# Dual_Power_Suppl_Center_T.net
KiCad netlist of a schematic drawn in EAGLE
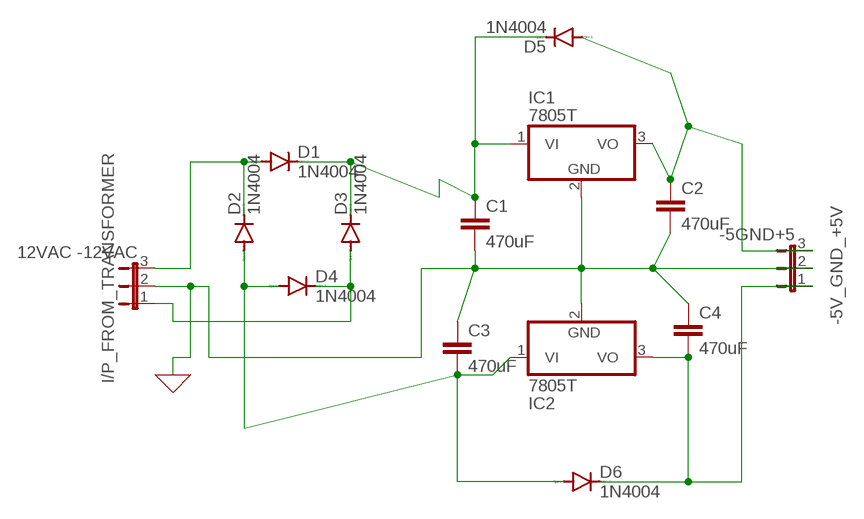
[diagram p0: schematic, sheet 1]

(export (version "E")
  (design (tool "Eeschema 10.0.6"))
  (components
    (comp (ref "-5V_GND_+5V")
      (value "-5GND+5")
      (footprint "eagle-import:JP2")
      (libsource (lib "eagle-import") (part "JP2E"))
    )
    (comp (ref "C1")
      (value "470uF")
      (footprint "eagle-import:C2.5-3")
      (libsource (lib "eagle-import") (part "C2,5-3"))
    )
    (comp (ref "C2")
      (value "470uF")
      (footprint "eagle-import:C2.5-3")
      (libsource (lib "eagle-import") (part "C2,5-3"))
    )
    (comp (ref "C3")
      (value "470uF")
      (footprint "eagle-import:C2.5-3")
      (libsource (lib "eagle-import") (part "C2,5-3"))
    )
    (comp (ref "C4")
      (value "470uF")
      (footprint "eagle-import:C2.5-3")
      (libsource (lib "eagle-import") (part "C2,5-3"))
    )
    (comp (ref "D1")
      (value "1N4004")
      (footprint "eagle-import:DO41-10")
      (libsource (lib "eagle-import") (part "1N4004"))
    )
    (comp (ref "D2")
      (value "1N4004")
      (footprint "eagle-import:DO41-10")
      (libsource (lib "eagle-import") (part "1N4004"))
    )
    (comp (ref "D3")
      (value "1N4004")
      (footprint "eagle-import:DO41-10")
      (libsource (lib "eagle-import") (part "1N4004"))
    )
    (comp (ref "D4")
      (value "1N4004")
      (footprint "eagle-import:DO41-10")
      (libsource (lib "eagle-import") (part "1N4004"))
    )
    (comp (ref "D5")
      (value "1N4004")
      (footprint "eagle-import:DO41-10")
      (libsource (lib "eagle-import") (part "1N4004"))
    )
    (comp (ref "D6")
      (value "1N4004")
      (footprint "eagle-import:DO41-10")
      (libsource (lib "eagle-import") (part "1N4004"))
    )
    (comp (ref "I/P_FROM_TRANSFORMER")
      (value "12VAC -12VAC")
      (footprint "eagle-import:JP2")
      (libsource (lib "eagle-import") (part "JP2E"))
    )
    (comp (ref "IC1")
      (value "7805T")
      (footprint "eagle-import:TO220H")
      (libsource (lib "eagle-import") (part "78T05"))
    )
    (comp (ref "IC2")
      (value "7805T")
      (footprint "eagle-import:TO220H")
      (libsource (lib "eagle-import") (part "78T05"))
    )
  )
  (nets
    (net (code "1") (name "GND") (class "Default")
      (node (ref "-5V_GND_+5V") (pin "2") (pinfunction "2_2") (pintype "passive"))
      (node (ref "C1") (pin "2") (pinfunction "2_2") (pintype "passive"))
      (node (ref "C2") (pin "2") (pinfunction "2_2") (pintype "passive"))
      (node (ref "C3") (pin "1") (pinfunction "1_1") (pintype "passive"))
      (node (ref "C4") (pin "1") (pinfunction "1_1") (pintype "passive"))
      (node (ref "I/P_FROM_TRANSFORMER") (pin "2") (pinfunction "2_2") (pintype "passive"))
      (node (ref "IC1") (pin "2") (pinfunction "GND_2") (pintype "passive"))
      (node (ref "IC2") (pin "2") (pinfunction "GND_2") (pintype "passive"))
    )
    (net (code "2") (name "Net-(D1-PadA)") (class "Default")
      (node (ref "D1") (pin "A") (pinfunction "A_A") (pintype "passive"))
      (node (ref "D2") (pin "C") (pinfunction "C_C") (pintype "passive"))
      (node (ref "I/P_FROM_TRANSFORMER") (pin "3") (pinfunction "3_3") (pintype "passive"))
    )
    (net (code "3") (name "Net-(D3-PadA)") (class "Default")
      (node (ref "D3") (pin "A") (pinfunction "A_A") (pintype "passive"))
      (node (ref "D4") (pin "C") (pinfunction "C_C") (pintype "passive"))
      (node (ref "I/P_FROM_TRANSFORMER") (pin "1") (pinfunction "1_1") (pintype "passive"))
    )
    (net (code "4") (name "Net-(IC1-VI)") (class "Default")
      (node (ref "C1") (pin "1") (pinfunction "1_1") (pintype "passive"))
      (node (ref "D1") (pin "C") (pinfunction "C_C") (pintype "passive"))
      (node (ref "D3") (pin "C") (pinfunction "C_C") (pintype "passive"))
      (node (ref "D5") (pin "C") (pinfunction "C_C") (pintype "passive"))
      (node (ref "IC1") (pin "1") (pinfunction "VI_1") (pintype "input"))
    )
    (net (code "5") (name "Net-(IC1-VO)") (class "Default")
      (node (ref "-5V_GND_+5V") (pin "3") (pinfunction "3_3") (pintype "passive"))
      (node (ref "C2") (pin "1") (pinfunction "1_1") (pintype "passive"))
      (node (ref "D5") (pin "A") (pinfunction "A_A") (pintype "passive"))
      (node (ref "IC1") (pin "3") (pinfunction "VO_3") (pintype "passive"))
    )
    (net (code "6") (name "Net-(IC2-VI)") (class "Default")
      (node (ref "C3") (pin "2") (pinfunction "2_2") (pintype "passive"))
      (node (ref "D2") (pin "A") (pinfunction "A_A") (pintype "passive"))
      (node (ref "D4") (pin "A") (pinfunction "A_A") (pintype "passive"))
      (node (ref "D6") (pin "A") (pinfunction "A_A") (pintype "passive"))
      (node (ref "IC2") (pin "1") (pinfunction "VI_1") (pintype "input"))
    )
    (net (code "7") (name "Net-(IC2-VO)") (class "Default")
      (node (ref "-5V_GND_+5V") (pin "1") (pinfunction "1_1") (pintype "passive"))
      (node (ref "C4") (pin "2") (pinfunction "2_2") (pintype "passive"))
      (node (ref "D6") (pin "C") (pinfunction "C_C") (pintype "passive"))
      (node (ref "IC2") (pin "3") (pinfunction "VO_3") (pintype "passive"))
    )
  )
)
